# DroneController.net
KiCad netlist of a schematic drawn in EAGLE
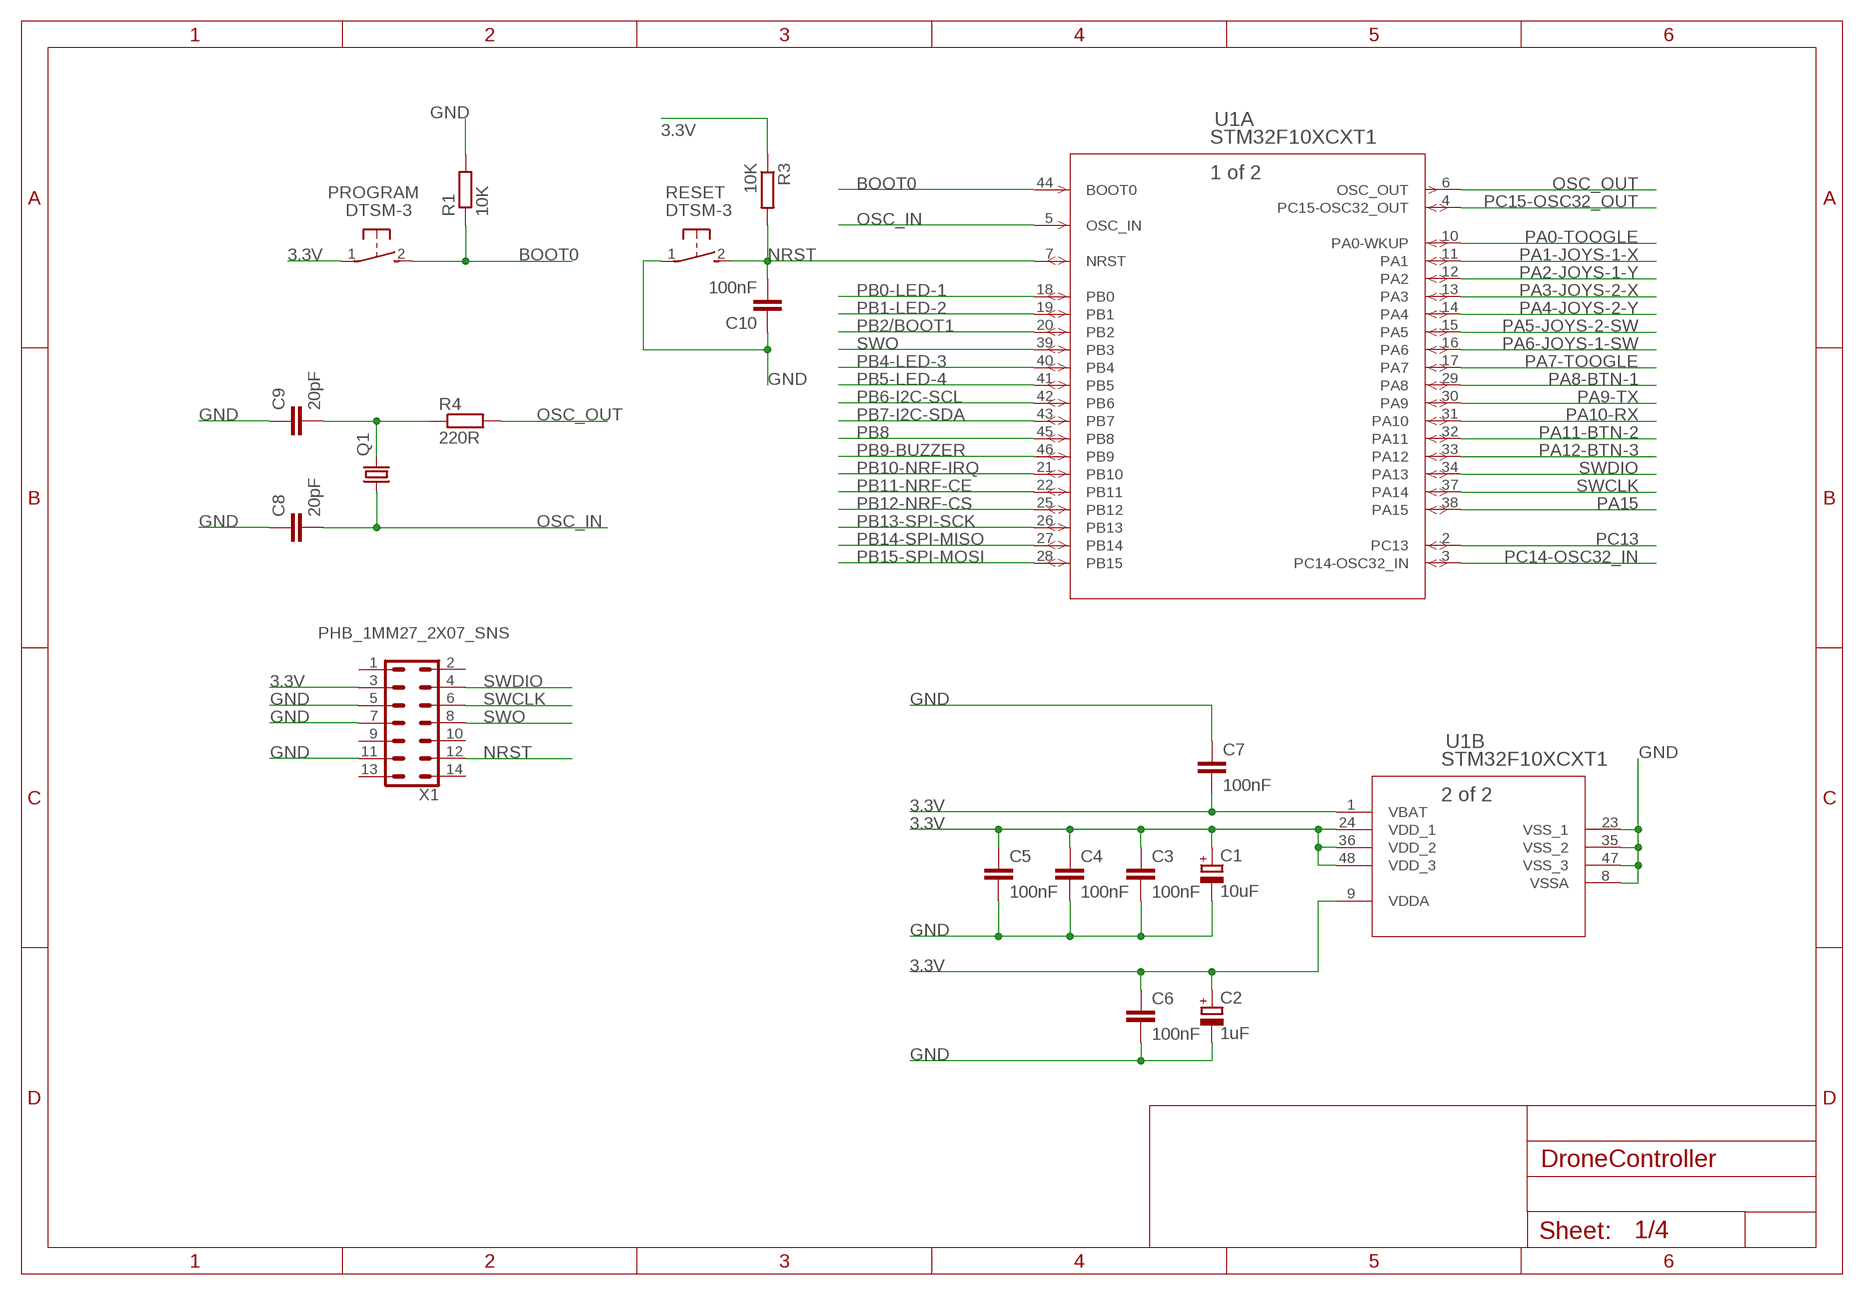
[diagram p0: schematic, sheet 1]
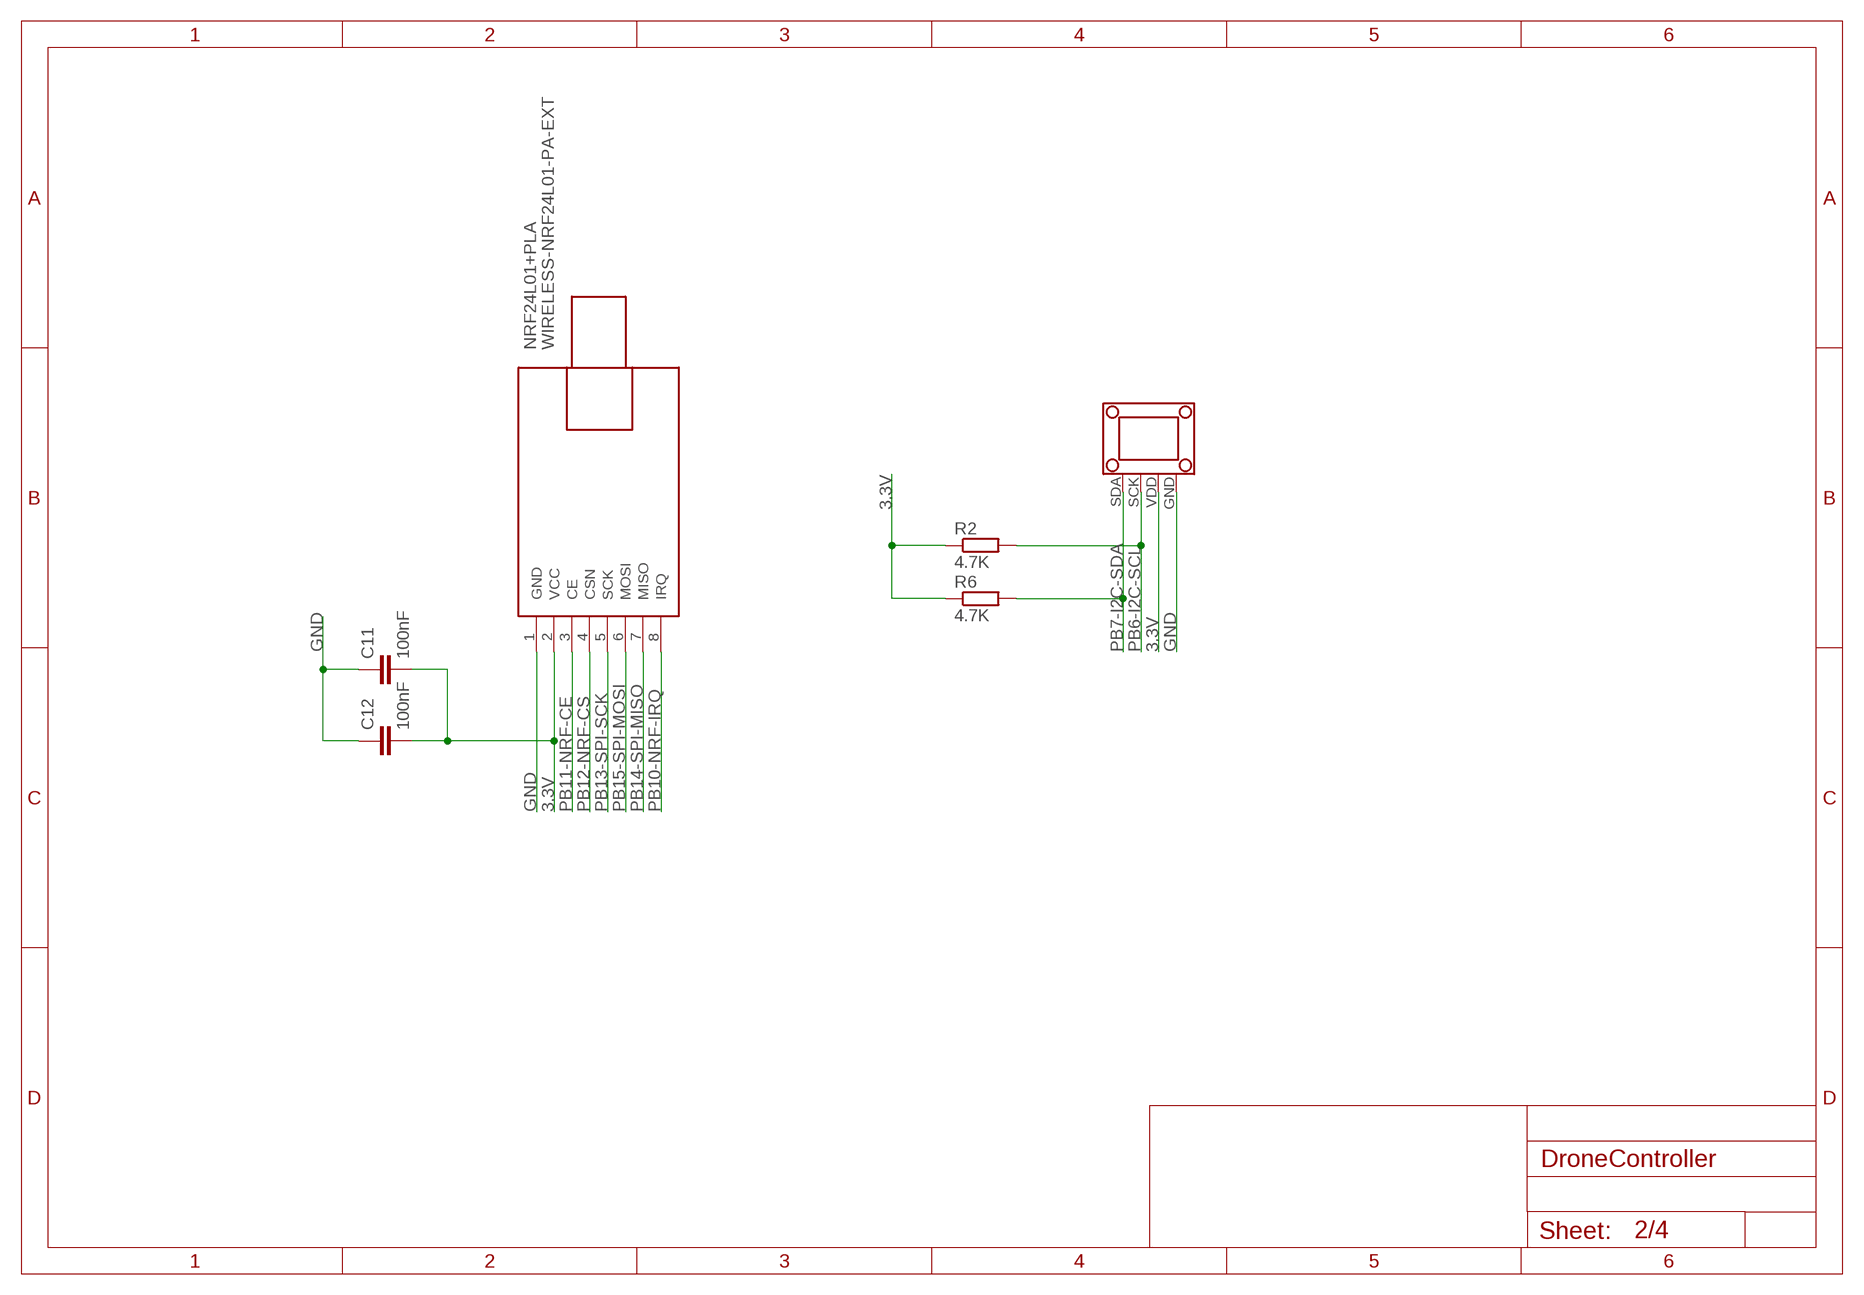
[diagram p1: schematic, sheet 2]
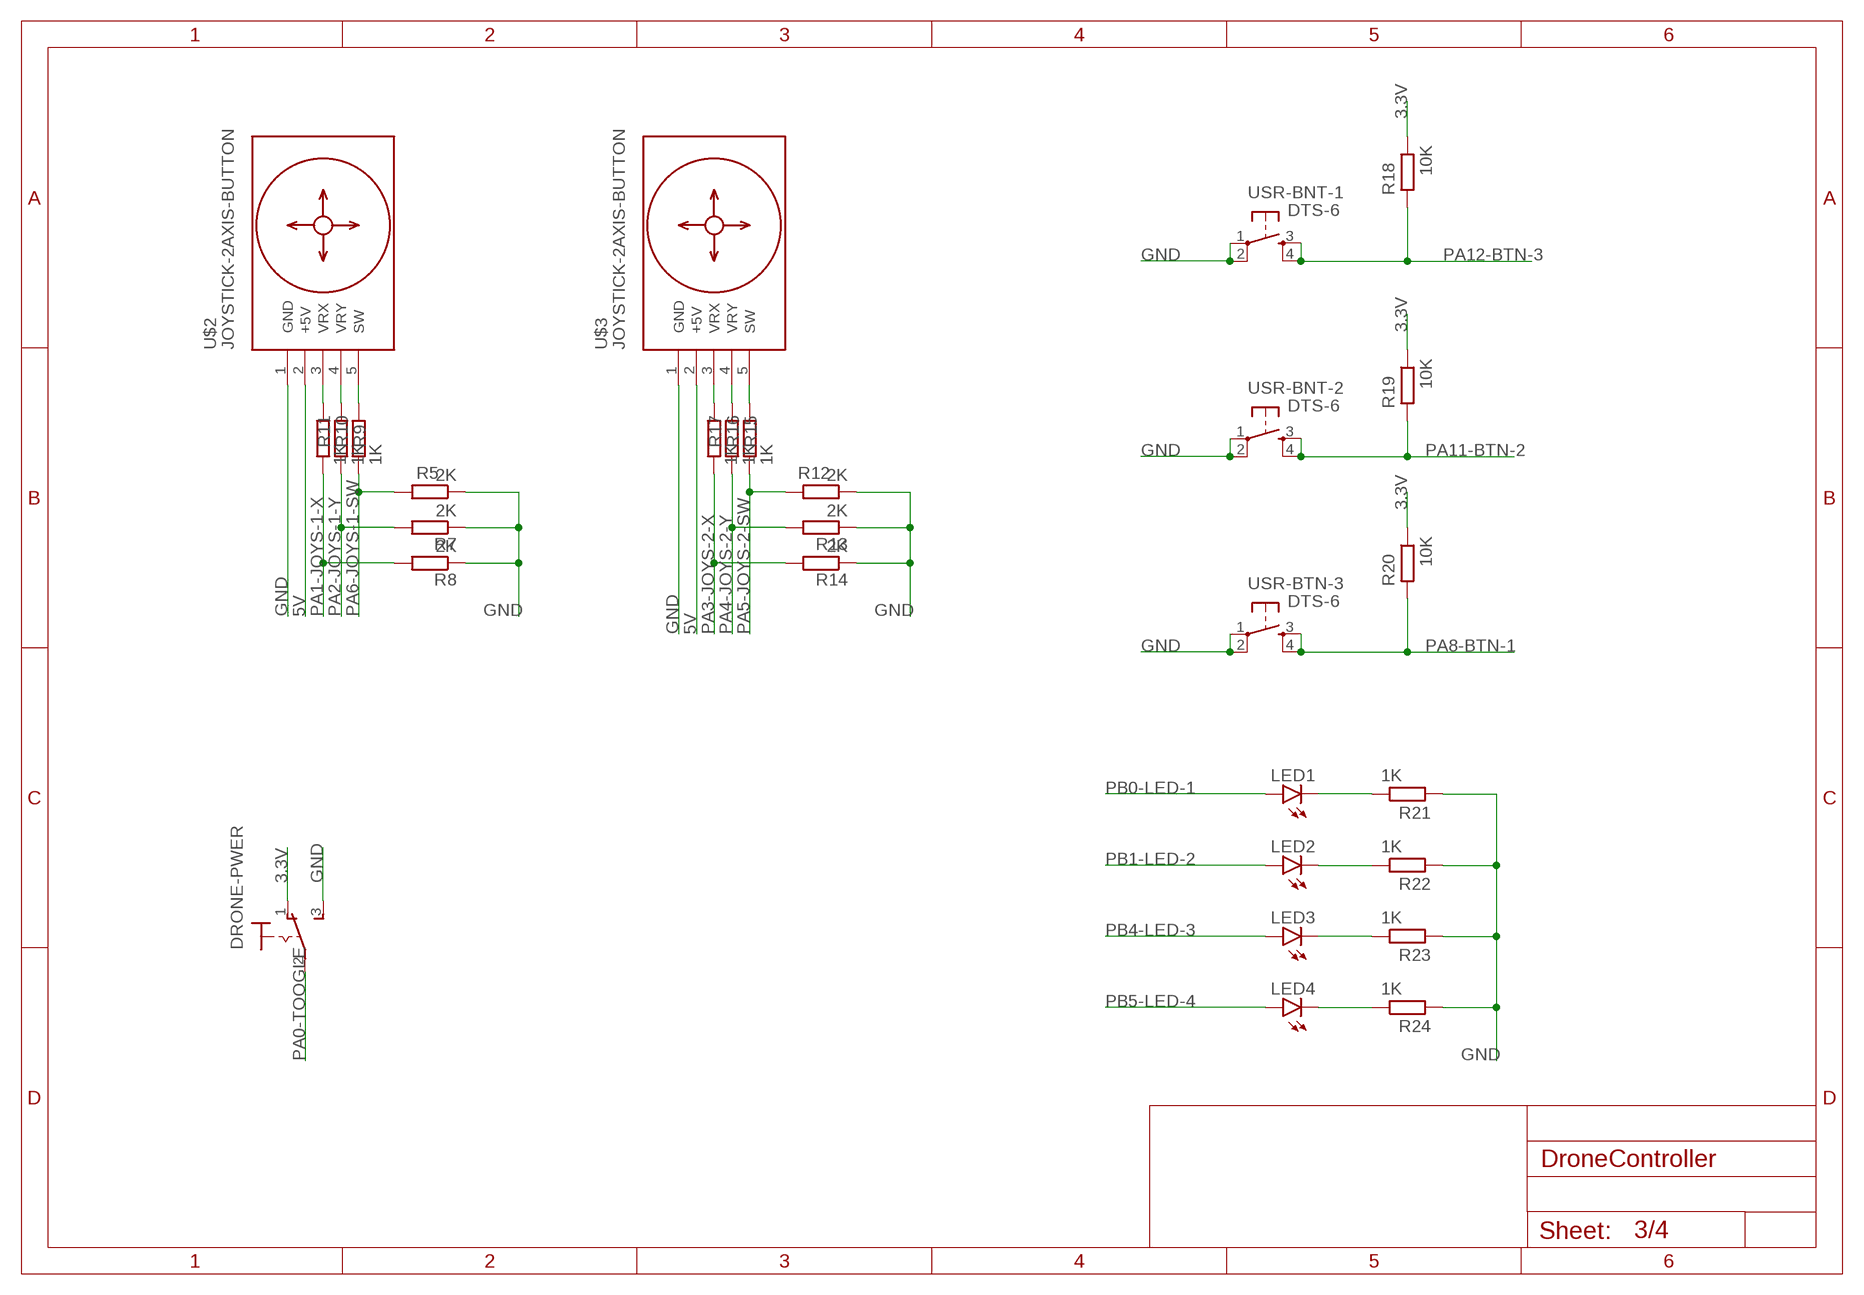
[diagram p2: schematic, sheet 3]
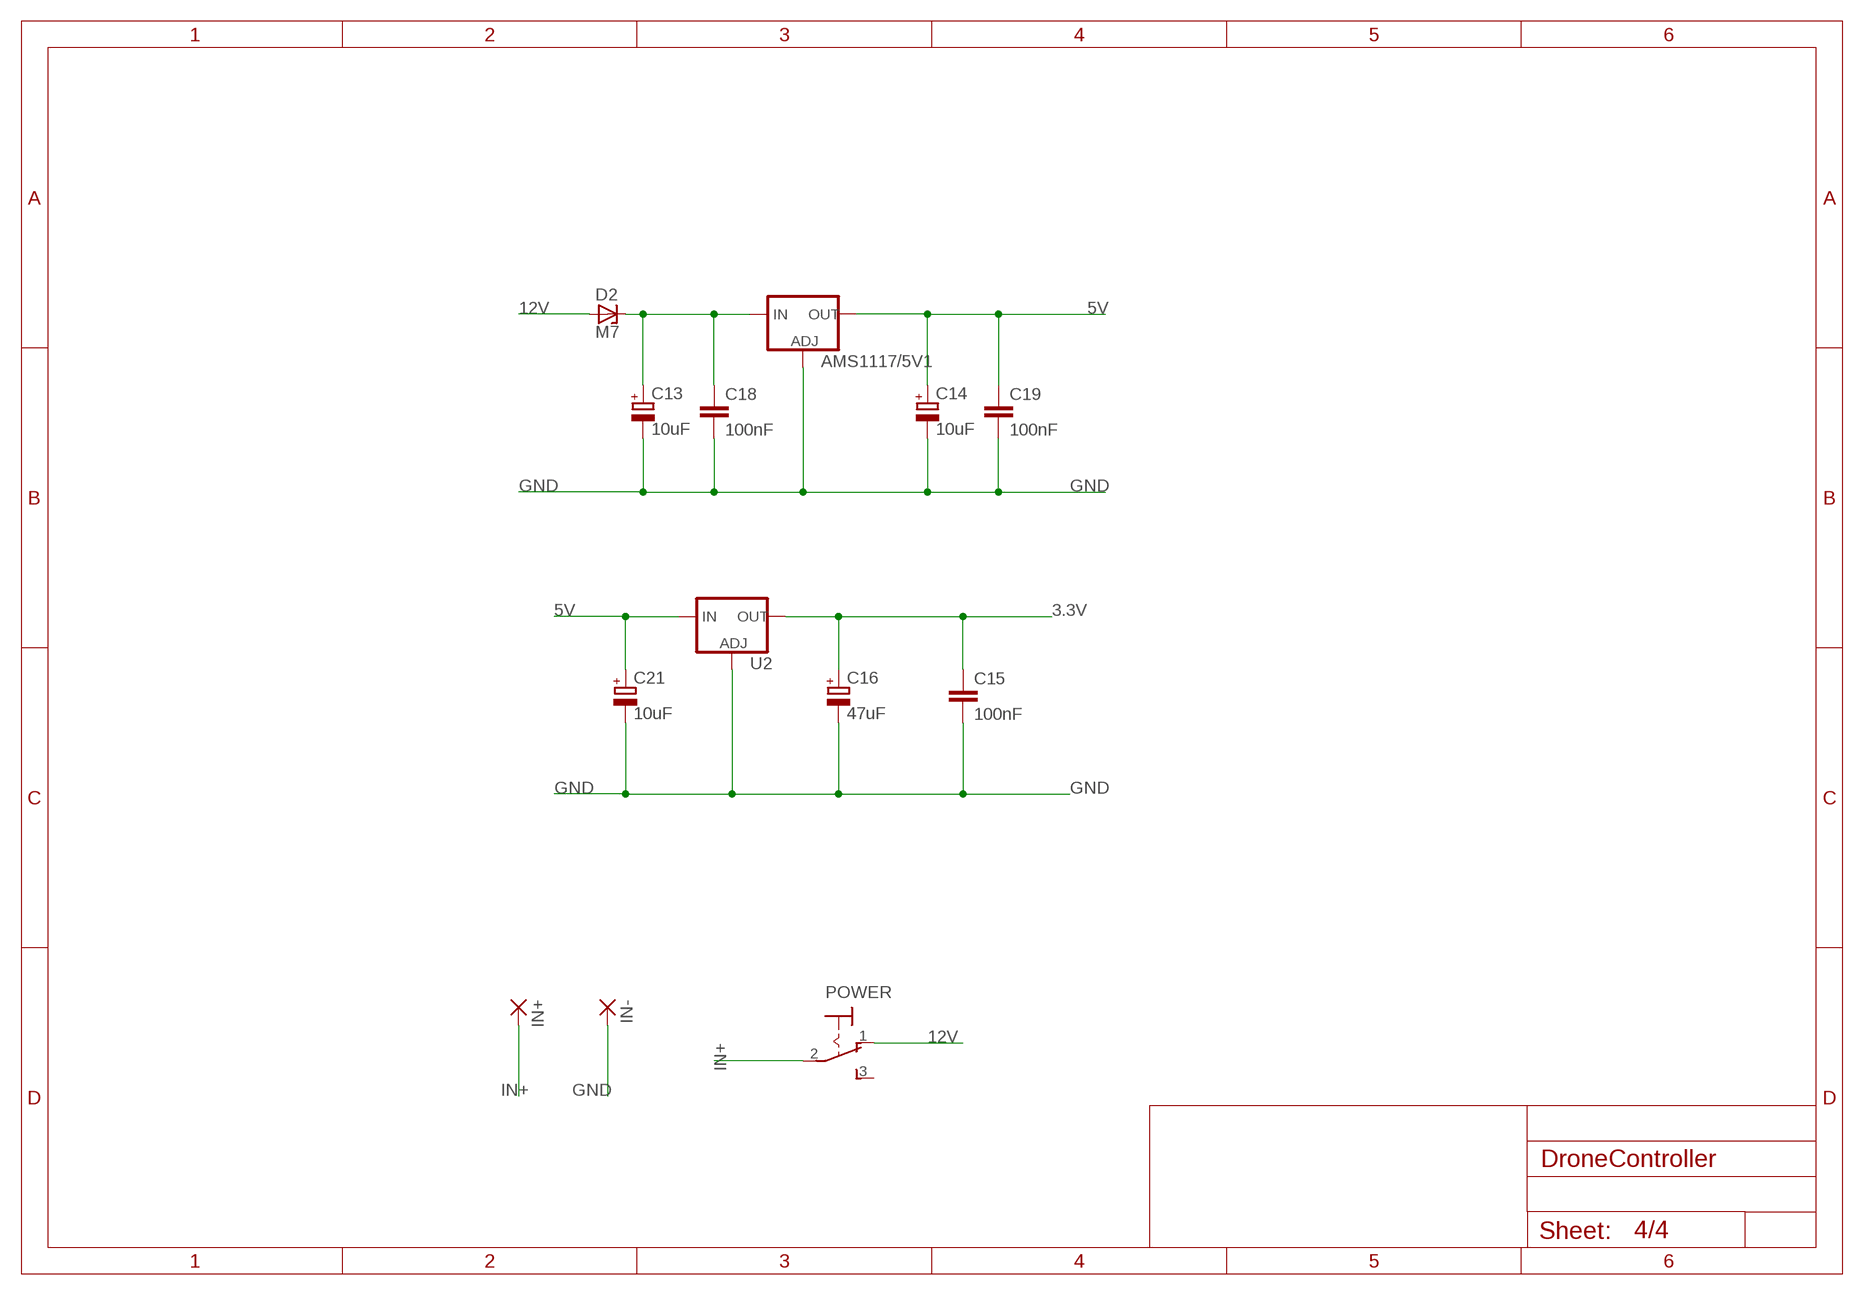
[diagram p3: schematic, sheet 4]

(export (version "E")
  (design (tool "Eeschema 10.0.6"))
  (components
    (comp (ref "DRONE-PWER")
      (value "M9040P")
      (footprint "eagle-import:M9040P")
      (libsource (lib "eagle-import") (part "M9040P"))
    )
    (comp (ref "LED1")
      (value "LEDCHIP-LED0805")
      (footprint "eagle-import:CHIP-LED0805")
      (libsource (lib "eagle-import") (part "LEDCHIP-LED0805"))
    )
    (comp (ref "LED2")
      (value "LEDCHIP-LED0805")
      (footprint "eagle-import:CHIP-LED0805")
      (libsource (lib "eagle-import") (part "LEDCHIP-LED0805"))
    )
    (comp (ref "LED3")
      (value "LEDCHIP-LED0805")
      (footprint "eagle-import:CHIP-LED0805")
      (libsource (lib "eagle-import") (part "LEDCHIP-LED0805"))
    )
    (comp (ref "LED4")
      (value "LEDCHIP-LED0805")
      (footprint "eagle-import:CHIP-LED0805")
      (libsource (lib "eagle-import") (part "LEDCHIP-LED0805"))
    )
    (comp (ref "R5")
      (value "2K")
      (footprint "eagle-import:R0805")
      (libsource (lib "eagle-import") (part "R-EU_R0805"))
    )
    (comp (ref "R7")
      (value "2K")
      (footprint "eagle-import:R0805")
      (libsource (lib "eagle-import") (part "R-EU_R0805"))
    )
    (comp (ref "R8")
      (value "2K")
      (footprint "eagle-import:R0805")
      (libsource (lib "eagle-import") (part "R-EU_R0805"))
    )
    (comp (ref "R9")
      (value "1K")
      (footprint "eagle-import:R0805")
      (libsource (lib "eagle-import") (part "R-EU_R0805"))
    )
    (comp (ref "R10")
      (value "1K")
      (footprint "eagle-import:R0805")
      (libsource (lib "eagle-import") (part "R-EU_R0805"))
    )
    (comp (ref "R11")
      (value "1K")
      (footprint "eagle-import:R0805")
      (libsource (lib "eagle-import") (part "R-EU_R0805"))
    )
    (comp (ref "R12")
      (value "2K")
      (footprint "eagle-import:R0805")
      (libsource (lib "eagle-import") (part "R-EU_R0805"))
    )
    (comp (ref "R13")
      (value "2K")
      (footprint "eagle-import:R0805")
      (libsource (lib "eagle-import") (part "R-EU_R0805"))
    )
    (comp (ref "R14")
      (value "2K")
      (footprint "eagle-import:R0805")
      (libsource (lib "eagle-import") (part "R-EU_R0805"))
    )
    (comp (ref "R15")
      (value "1K")
      (footprint "eagle-import:R0805")
      (libsource (lib "eagle-import") (part "R-EU_R0805"))
    )
    (comp (ref "R16")
      (value "1K")
      (footprint "eagle-import:R0805")
      (libsource (lib "eagle-import") (part "R-EU_R0805"))
    )
    (comp (ref "R17")
      (value "1K")
      (footprint "eagle-import:R0805")
      (libsource (lib "eagle-import") (part "R-EU_R0805"))
    )
    (comp (ref "R18")
      (value "10K")
      (footprint "eagle-import:R0805")
      (libsource (lib "eagle-import") (part "R-EU_R0805"))
    )
    (comp (ref "R19")
      (value "10K")
      (footprint "eagle-import:R0805")
      (libsource (lib "eagle-import") (part "R-EU_R0805"))
    )
    (comp (ref "R20")
      (value "10K")
      (footprint "eagle-import:R0805")
      (libsource (lib "eagle-import") (part "R-EU_R0805"))
    )
    (comp (ref "R21")
      (value "1K")
      (footprint "eagle-import:R0805")
      (libsource (lib "eagle-import") (part "R-EU_R0805"))
    )
    (comp (ref "R22")
      (value "1K")
      (footprint "eagle-import:R0805")
      (libsource (lib "eagle-import") (part "R-EU_R0805"))
    )
    (comp (ref "R23")
      (value "1K")
      (footprint "eagle-import:R0805")
      (libsource (lib "eagle-import") (part "R-EU_R0805"))
    )
    (comp (ref "R24")
      (value "1K")
      (footprint "eagle-import:R0805")
      (libsource (lib "eagle-import") (part "R-EU_R0805"))
    )
    (comp (ref "U$2")
      (value "JOYSTICK-2AXIS-BUTTON")
      (footprint "eagle-import:JOYSTICK-2AXIS-BUTTON")
      (libsource (lib "eagle-import") (part "JOYSTICK-2AXIS-BUTTON"))
    )
    (comp (ref "U$3")
      (value "JOYSTICK-2AXIS-BUTTON")
      (footprint "eagle-import:JOYSTICK-2AXIS-BUTTON")
      (libsource (lib "eagle-import") (part "JOYSTICK-2AXIS-BUTTON"))
    )
    (comp (ref "USR-BNT-1")
      (value "DTS-6")
      (footprint "eagle-import:DTS-6")
      (libsource (lib "eagle-import") (part "DTS-6"))
    )
    (comp (ref "USR-BNT-2")
      (value "DTS-6")
      (footprint "eagle-import:DTS-6")
      (libsource (lib "eagle-import") (part "DTS-6"))
    )
    (comp (ref "USR-BTN-3")
      (value "DTS-6")
      (footprint "eagle-import:DTS-6")
      (libsource (lib "eagle-import") (part "DTS-6"))
    )
    (comp (ref "AMS1117/5V1")
      (value "V_REG_LM1117SOT223")
      (footprint "eagle-import:SOT223")
      (libsource (lib "eagle-import") (part "V_REG_LM1117SOT223"))
    )
    (comp (ref "C13")
      (value "10uF")
      (footprint "eagle-import:SMC_A")
      (libsource (lib "eagle-import") (part "CPOL-EUSMCA"))
    )
    (comp (ref "C14")
      (value "10uF")
      (footprint "eagle-import:SMC_A")
      (libsource (lib "eagle-import") (part "CPOL-EUSMCA"))
    )
    (comp (ref "C15")
      (value "100nF")
      (footprint "eagle-import:C0805")
      (libsource (lib "eagle-import") (part "C-EUC0805"))
    )
    (comp (ref "C16")
      (value "47uF")
      (footprint "eagle-import:SMC_B")
      (libsource (lib "eagle-import") (part "CPOL-EUSMCB"))
    )
    (comp (ref "C18")
      (value "100nF")
      (footprint "eagle-import:C0805")
      (libsource (lib "eagle-import") (part "C-EUC0805"))
    )
    (comp (ref "C19")
      (value "100nF")
      (footprint "eagle-import:C0805")
      (libsource (lib "eagle-import") (part "C-EUC0805"))
    )
    (comp (ref "C21")
      (value "10uF")
      (footprint "eagle-import:SMC_A")
      (libsource (lib "eagle-import") (part "CPOL-EUSMCA"))
    )
    (comp (ref "D2")
      (value "M7")
      (footprint "eagle-import:DO214AC")
      (fields (field (name "MF") "ON Semiconductor") (field (name "MPN") "1SMA5913BT3G"))
      (libsource (lib "eagle-import") (part "1SMA59BT3G13"))
    )
    (comp (ref "IN+")
      (value "2,15/1,0")
      (footprint "eagle-import:2,15_1,0")
      (libsource (lib "eagle-import") (part "2,15/1,0"))
    )
    (comp (ref "IN-")
      (value "2,15/1,0")
      (footprint "eagle-import:2,15_1,0")
      (libsource (lib "eagle-import") (part "2,15/1,0"))
    )
    (comp (ref "POWER")
      (value "M9040P")
      (footprint "eagle-import:M9040P")
      (libsource (lib "eagle-import") (part "M9040P"))
    )
    (comp (ref "U2")
      (value "V_REG_LM1117SOT223")
      (footprint "eagle-import:SOT223")
      (libsource (lib "eagle-import") (part "V_REG_LM1117SOT223"))
    )
    (comp (ref "C11")
      (value "100nF")
      (footprint "eagle-import:C0805")
      (libsource (lib "eagle-import") (part "C-EUC0805"))
    )
    (comp (ref "C12")
      (value "100nF")
      (footprint "eagle-import:C0805")
      (libsource (lib "eagle-import") (part "C-EUC0805"))
    )
    (comp (ref "NRF24L01+PLA")
      (value "WIRELESS-NRF24L01-PA-EXT")
      (footprint "eagle-import:WIRELESS-NRF24L01-PA-EXT")
      (libsource (lib "eagle-import") (part "WIRELESS-NRF24L01-PA-EXT"))
    )
    (comp (ref "R2")
      (value "4.7K")
      (footprint "eagle-import:R0805")
      (libsource (lib "eagle-import") (part "R-EU_R0805"))
    )
    (comp (ref "R6")
      (value "4.7K")
      (footprint "eagle-import:R0805")
      (libsource (lib "eagle-import") (part "R-EU_R0805"))
    )
    (comp (ref "U$1")
      (value "1.3_TFT_OLED")
      (footprint "eagle-import:1.3_TFT_OLED")
      (libsource (lib "eagle-import") (part "1.3_TFT_OLED"))
    )
    (comp (ref "C1")
      (value "10uF")
      (footprint "eagle-import:SMC_A")
      (libsource (lib "eagle-import") (part "CPOL-EUSMCA"))
    )
    (comp (ref "C2")
      (value "1uF")
      (footprint "eagle-import:SMC_A")
      (libsource (lib "eagle-import") (part "CPOL-EUSMCA"))
    )
    (comp (ref "C3")
      (value "100nF")
      (footprint "eagle-import:C0805")
      (libsource (lib "eagle-import") (part "C-EUC0805"))
    )
    (comp (ref "C4")
      (value "100nF")
      (footprint "eagle-import:C0805")
      (libsource (lib "eagle-import") (part "C-EUC0805"))
    )
    (comp (ref "C5")
      (value "100nF")
      (footprint "eagle-import:C0805")
      (libsource (lib "eagle-import") (part "C-EUC0805"))
    )
    (comp (ref "C6")
      (value "100nF")
      (footprint "eagle-import:C0805")
      (libsource (lib "eagle-import") (part "C-EUC0805"))
    )
    (comp (ref "C7")
      (value "100nF")
      (footprint "eagle-import:C0805")
      (libsource (lib "eagle-import") (part "C-EUC0805"))
    )
    (comp (ref "C8")
      (value "20pF")
      (footprint "eagle-import:C0805")
      (libsource (lib "eagle-import") (part "C-EUC0805"))
    )
    (comp (ref "C9")
      (value "20pF")
      (footprint "eagle-import:C0805")
      (libsource (lib "eagle-import") (part "C-EUC0805"))
    )
    (comp (ref "C10")
      (value "100nF")
      (footprint "eagle-import:C0805")
      (libsource (lib "eagle-import") (part "C-EUC0805"))
    )
    (comp (ref "PROGRAM")
      (value "DTSM-3")
      (footprint "eagle-import:DTSM-3")
      (libsource (lib "eagle-import") (part "DTSM-3"))
    )
    (comp (ref "Q1")
      (value "CRYSTALHC49S")
      (footprint "eagle-import:HC49_S")
      (libsource (lib "eagle-import") (part "CRYSTALHC49S"))
    )
    (comp (ref "R1")
      (value "10K")
      (footprint "eagle-import:R0805")
      (libsource (lib "eagle-import") (part "R-EU_R0805"))
    )
    (comp (ref "R3")
      (value "10K")
      (footprint "eagle-import:R0805")
      (libsource (lib "eagle-import") (part "R-EU_R0805"))
    )
    (comp (ref "R4")
      (value "220R")
      (footprint "eagle-import:R0805")
      (libsource (lib "eagle-import") (part "R-EU_R0805"))
    )
    (comp (ref "RESET")
      (value "DTSM-3")
      (footprint "eagle-import:DTSM-3")
      (libsource (lib "eagle-import") (part "DTSM-3"))
    )
    (comp (ref "U1")
      (value "STM32F10XCXT1")
      (footprint "eagle-import:LQFP48-7X7MM")
      (fields (field (name "COPYRIGHT") "Copyright (C) 2016 Accelerated Designs. All rights reserved"))
      (libsource (lib "eagle-import") (part "STM32F10XCXT1"))
    )
    (comp (ref "X1")
      (value "PHB_1MM27_2X07_SNS")
      (footprint "eagle-import:PHB_1MM27_2X07_SNS")
      (libsource (lib "eagle-import") (part "PHB_1MM27_2X07_SNS"))
    )
  )
  (nets
    (net (code "1") (name "3.3V") (class "Default")
      (node (ref "C1") (pin "+") (pinfunction "+_+") (pintype "passive"))
      (node (ref "C11") (pin "2") (pinfunction "2_2") (pintype "passive"))
      (node (ref "C12") (pin "2") (pinfunction "2_2") (pintype "passive"))
      (node (ref "C15") (pin "1") (pinfunction "1_1") (pintype "passive"))
      (node (ref "C16") (pin "+") (pinfunction "+_+") (pintype "passive"))
      (node (ref "C2") (pin "+") (pinfunction "+_+") (pintype "passive"))
      (node (ref "C3") (pin "1") (pinfunction "1_1") (pintype "passive"))
      (node (ref "C4") (pin "1") (pinfunction "1_1") (pintype "passive"))
      (node (ref "C5") (pin "1") (pinfunction "1_1") (pintype "passive"))
      (node (ref "C6") (pin "1") (pinfunction "1_1") (pintype "passive"))
      (node (ref "C7") (pin "2") (pinfunction "2_2") (pintype "passive"))
      (node (ref "DRONE-PWER") (pin "1") (pinfunction "O_1") (pintype "passive"))
      (node (ref "NRF24L01+PLA") (pin "2") (pinfunction "VCC_2") (pintype "power_in"))
      (node (ref "PROGRAM") (pin "1") (pinfunction "1_1") (pintype "passive"))
      (node (ref "R18") (pin "1") (pinfunction "1_1") (pintype "passive"))
      (node (ref "R19") (pin "1") (pinfunction "1_1") (pintype "passive"))
      (node (ref "R2") (pin "1") (pinfunction "1_1") (pintype "passive"))
      (node (ref "R20") (pin "1") (pinfunction "1_1") (pintype "passive"))
      (node (ref "R3") (pin "1") (pinfunction "1_1") (pintype "passive"))
      (node (ref "R6") (pin "1") (pinfunction "1_1") (pintype "passive"))
      (node (ref "U$1") (pin "VDD") (pinfunction "VDD_VDD") (pintype "bidirectional"))
      (node (ref "U1") (pin "1") (pinfunction "VBAT_1") (pintype "power_in"))
      (node (ref "U1") (pin "24") (pinfunction "VDD_1_24") (pintype "power_in"))
      (node (ref "U1") (pin "36") (pinfunction "VDD_2_36") (pintype "power_in"))
      (node (ref "U1") (pin "48") (pinfunction "VDD_3_48") (pintype "power_in"))
      (node (ref "U1") (pin "9") (pinfunction "VDDA_9") (pintype "power_in"))
      (node (ref "U2") (pin "2") (pinfunction "OUT_2") (pintype "output"))
      (node (ref "U2") (pin "4") (pinfunction "OUT_4") (pintype "output"))
      (node (ref "X1") (pin "3") (pinfunction "3_3") (pintype "passive"))
    )
    (net (code "2") (name "5V") (class "Default")
      (node (ref "AMS1117/5V1") (pin "2") (pinfunction "OUT_2") (pintype "output"))
      (node (ref "AMS1117/5V1") (pin "4") (pinfunction "OUT_4") (pintype "output"))
      (node (ref "C14") (pin "+") (pinfunction "+_+") (pintype "passive"))
      (node (ref "C19") (pin "1") (pinfunction "1_1") (pintype "passive"))
      (node (ref "C21") (pin "+") (pinfunction "+_+") (pintype "passive"))
      (node (ref "U$2") (pin "2") (pinfunction "+5V_2") (pintype "power_in"))
      (node (ref "U$3") (pin "2") (pinfunction "+5V_2") (pintype "power_in"))
      (node (ref "U2") (pin "3") (pinfunction "IN_3") (pintype "input"))
    )
    (net (code "3") (name "12V") (class "Default")
      (node (ref "D2") (pin "A") (pinfunction "A_A") (pintype "passive"))
      (node (ref "POWER") (pin "1") (pinfunction "O_1") (pintype "passive"))
    )
    (net (code "4") (name "BOOT0") (class "Default")
      (node (ref "PROGRAM") (pin "2") (pinfunction "2_2") (pintype "passive"))
      (node (ref "R1") (pin "1") (pinfunction "1_1") (pintype "passive"))
      (node (ref "U1") (pin "44") (pinfunction "BOOT0_44") (pintype "input"))
    )
    (net (code "5") (name "GND") (class "Default")
      (node (ref "AMS1117/5V1") (pin "1") (pinfunction "ADJ_1") (pintype "input"))
      (node (ref "C1") (pin "-") (pinfunction "-_-") (pintype "passive"))
      (node (ref "C10") (pin "1") (pinfunction "1_1") (pintype "passive"))
      (node (ref "C11") (pin "1") (pinfunction "1_1") (pintype "passive"))
      (node (ref "C12") (pin "1") (pinfunction "1_1") (pintype "passive"))
      (node (ref "C13") (pin "-") (pinfunction "-_-") (pintype "passive"))
      (node (ref "C14") (pin "-") (pinfunction "-_-") (pintype "passive"))
      (node (ref "C15") (pin "2") (pinfunction "2_2") (pintype "passive"))
      (node (ref "C16") (pin "-") (pinfunction "-_-") (pintype "passive"))
      (node (ref "C18") (pin "2") (pinfunction "2_2") (pintype "passive"))
      (node (ref "C19") (pin "2") (pinfunction "2_2") (pintype "passive"))
      (node (ref "C2") (pin "-") (pinfunction "-_-") (pintype "passive"))
      (node (ref "C21") (pin "-") (pinfunction "-_-") (pintype "passive"))
      (node (ref "C3") (pin "2") (pinfunction "2_2") (pintype "passive"))
      (node (ref "C4") (pin "2") (pinfunction "2_2") (pintype "passive"))
      (node (ref "C5") (pin "2") (pinfunction "2_2") (pintype "passive"))
      (node (ref "C6") (pin "2") (pinfunction "2_2") (pintype "passive"))
      (node (ref "C7") (pin "1") (pinfunction "1_1") (pintype "passive"))
      (node (ref "C8") (pin "1") (pinfunction "1_1") (pintype "passive"))
      (node (ref "C9") (pin "1") (pinfunction "1_1") (pintype "passive"))
      (node (ref "DRONE-PWER") (pin "3") (pinfunction "S_3") (pintype "passive"))
      (node (ref "IN-") (pin "1") (pinfunction "P_1") (pintype "passive"))
      (node (ref "NRF24L01+PLA") (pin "1") (pinfunction "GND_1") (pintype "power_in"))
      (node (ref "R1") (pin "2") (pinfunction "2_2") (pintype "passive"))
      (node (ref "R12") (pin "1") (pinfunction "1_1") (pintype "passive"))
      (node (ref "R13") (pin "1") (pinfunction "1_1") (pintype "passive"))
      (node (ref "R14") (pin "1") (pinfunction "1_1") (pintype "passive"))
      (node (ref "R21") (pin "2") (pinfunction "2_2") (pintype "passive"))
      (node (ref "R22") (pin "2") (pinfunction "2_2") (pintype "passive"))
      (node (ref "R23") (pin "2") (pinfunction "2_2") (pintype "passive"))
      (node (ref "R24") (pin "2") (pinfunction "2_2") (pintype "passive"))
      (node (ref "R5") (pin "1") (pinfunction "1_1") (pintype "passive"))
      (node (ref "R7") (pin "1") (pinfunction "1_1") (pintype "passive"))
      (node (ref "R8") (pin "1") (pinfunction "1_1") (pintype "passive"))
      (node (ref "RESET") (pin "1") (pinfunction "1_1") (pintype "passive"))
      (node (ref "U$1") (pin "GND") (pinfunction "GND_GND") (pintype "bidirectional"))
      (node (ref "U$2") (pin "1") (pinfunction "GND_1") (pintype "power_in"))
      (node (ref "U$3") (pin "1") (pinfunction "GND_1") (pintype "power_in"))
      (node (ref "U1") (pin "23") (pinfunction "VSS_1_23") (pintype "power_in"))
      (node (ref "U1") (pin "35") (pinfunction "VSS_2_35") (pintype "power_in"))
      (node (ref "U1") (pin "47") (pinfunction "VSS_3_47") (pintype "power_in"))
      (node (ref "U1") (pin "8") (pinfunction "VSSA_8") (pintype "power_in"))
      (node (ref "U2") (pin "1") (pinfunction "ADJ_1") (pintype "input"))
      (node (ref "USR-BNT-1") (pin "1") (pinfunction "1_1") (pintype "passive"))
      (node (ref "USR-BNT-1") (pin "2") (pinfunction "2_2") (pintype "passive"))
      (node (ref "USR-BNT-2") (pin "1") (pinfunction "1_1") (pintype "passive"))
      (node (ref "USR-BNT-2") (pin "2") (pinfunction "2_2") (pintype "passive"))
      (node (ref "USR-BTN-3") (pin "1") (pinfunction "1_1") (pintype "passive"))
      (node (ref "USR-BTN-3") (pin "2") (pinfunction "2_2") (pintype "passive"))
      (node (ref "X1") (pin "11") (pinfunction "11_11") (pintype "passive"))
      (node (ref "X1") (pin "5") (pinfunction "5_5") (pintype "passive"))
      (node (ref "X1") (pin "7") (pinfunction "7_7") (pintype "passive"))
    )
    (net (code "6") (name "IN+") (class "Default")
      (node (ref "IN+") (pin "1") (pinfunction "P_1") (pintype "passive"))
      (node (ref "POWER") (pin "2") (pinfunction "P_2") (pintype "passive"))
    )
    (net (code "7") (name "NRST") (class "Default")
      (node (ref "C10") (pin "2") (pinfunction "2_2") (pintype "passive"))
      (node (ref "R3") (pin "2") (pinfunction "2_2") (pintype "passive"))
      (node (ref "RESET") (pin "2") (pinfunction "2_2") (pintype "passive"))
      (node (ref "U1") (pin "7") (pinfunction "NRST_7") (pintype "bidirectional"))
      (node (ref "X1") (pin "12") (pinfunction "12_12") (pintype "passive"))
    )
    (net (code "8") (name "Net-(AMS1117/5V1-IN)") (class "Default")
      (node (ref "AMS1117/5V1") (pin "3") (pinfunction "IN_3") (pintype "input"))
      (node (ref "C13") (pin "+") (pinfunction "+_+") (pintype "passive"))
      (node (ref "C18") (pin "1") (pinfunction "1_1") (pintype "passive"))
      (node (ref "D2") (pin "C") (pinfunction "C_C") (pintype "passive"))
    )
    (net (code "9") (name "Net-(C9-Pad2)") (class "Default")
      (node (ref "C9") (pin "2") (pinfunction "2_2") (pintype "passive"))
      (node (ref "Q1") (pin "2") (pinfunction "2_2") (pintype "passive"))
      (node (ref "R4") (pin "1") (pinfunction "1_1") (pintype "passive"))
    )
    (net (code "10") (name "Net-(LED1-PadC)") (class "Default")
      (node (ref "LED1") (pin "C") (pinfunction "C_C") (pintype "passive"))
      (node (ref "R21") (pin "1") (pinfunction "1_1") (pintype "passive"))
    )
    (net (code "11") (name "Net-(LED2-PadC)") (class "Default")
      (node (ref "LED2") (pin "C") (pinfunction "C_C") (pintype "passive"))
      (node (ref "R22") (pin "1") (pinfunction "1_1") (pintype "passive"))
    )
    (net (code "12") (name "Net-(LED3-PadC)") (class "Default")
      (node (ref "LED3") (pin "C") (pinfunction "C_C") (pintype "passive"))
      (node (ref "R23") (pin "1") (pinfunction "1_1") (pintype "passive"))
    )
    (net (code "13") (name "Net-(LED4-PadC)") (class "Default")
      (node (ref "LED4") (pin "C") (pinfunction "C_C") (pintype "passive"))
      (node (ref "R24") (pin "1") (pinfunction "1_1") (pintype "passive"))
    )
    (net (code "14") (name "Net-(U$2-SW)") (class "Default")
      (node (ref "R9") (pin "2") (pinfunction "2_2") (pintype "passive"))
      (node (ref "U$2") (pin "5") (pinfunction "SW_5") (pintype "passive"))
    )
    (net (code "15") (name "Net-(U$2-VRX)") (class "Default")
      (node (ref "R11") (pin "2") (pinfunction "2_2") (pintype "passive"))
      (node (ref "U$2") (pin "3") (pinfunction "VRX_3") (pintype "passive"))
    )
    (net (code "16") (name "Net-(U$2-VRY)") (class "Default")
      (node (ref "R10") (pin "2") (pinfunction "2_2") (pintype "passive"))
      (node (ref "U$2") (pin "4") (pinfunction "VRY_4") (pintype "passive"))
    )
    (net (code "17") (name "Net-(U$3-SW)") (class "Default")
      (node (ref "R15") (pin "2") (pinfunction "2_2") (pintype "passive"))
      (node (ref "U$3") (pin "5") (pinfunction "SW_5") (pintype "passive"))
    )
    (net (code "18") (name "Net-(U$3-VRX)") (class "Default")
      (node (ref "R17") (pin "2") (pinfunction "2_2") (pintype "passive"))
      (node (ref "U$3") (pin "3") (pinfunction "VRX_3") (pintype "passive"))
    )
    (net (code "19") (name "Net-(U$3-VRY)") (class "Default")
      (node (ref "R16") (pin "2") (pinfunction "2_2") (pintype "passive"))
      (node (ref "U$3") (pin "4") (pinfunction "VRY_4") (pintype "passive"))
    )
    (net (code "20") (name "OSC_IN") (class "Default")
      (node (ref "C8") (pin "2") (pinfunction "2_2") (pintype "passive"))
      (node (ref "Q1") (pin "1") (pinfunction "1_1") (pintype "passive"))
      (node (ref "U1") (pin "5") (pinfunction "OSC_IN_5") (pintype "input"))
    )
    (net (code "21") (name "OSC_OUT") (class "Default")
      (node (ref "R4") (pin "2") (pinfunction "2_2") (pintype "passive"))
      (node (ref "U1") (pin "6") (pinfunction "OSC_OUT_6") (pintype "output"))
    )
    (net (code "22") (name "PA0-TOOGLE") (class "Default")
      (node (ref "DRONE-PWER") (pin "2") (pinfunction "P_2") (pintype "passive"))
      (node (ref "U1") (pin "10") (pinfunction "PA0-WKUP_10") (pintype "bidirectional"))
    )
    (net (code "23") (name "PA1-JOYS-1-X") (class "Default")
      (node (ref "R11") (pin "1") (pinfunction "1_1") (pintype "passive"))
      (node (ref "R8") (pin "2") (pinfunction "2_2") (pintype "passive"))
      (node (ref "U1") (pin "11") (pinfunction "PA1_11") (pintype "bidirectional"))
    )
    (net (code "24") (name "PA2-JOYS-1-Y") (class "Default")
      (node (ref "R10") (pin "1") (pinfunction "1_1") (pintype "passive"))
      (node (ref "R7") (pin "2") (pinfunction "2_2") (pintype "passive"))
      (node (ref "U1") (pin "12") (pinfunction "PA2_12") (pintype "bidirectional"))
    )
    (net (code "25") (name "PA3-JOYS-2-X") (class "Default")
      (node (ref "R14") (pin "2") (pinfunction "2_2") (pintype "passive"))
      (node (ref "R17") (pin "1") (pinfunction "1_1") (pintype "passive"))
      (node (ref "U1") (pin "13") (pinfunction "PA3_13") (pintype "bidirectional"))
    )
    (net (code "26") (name "PA4-JOYS-2-Y") (class "Default")
      (node (ref "R13") (pin "2") (pinfunction "2_2") (pintype "passive"))
      (node (ref "R16") (pin "1") (pinfunction "1_1") (pintype "passive"))
      (node (ref "U1") (pin "14") (pinfunction "PA4_14") (pintype "bidirectional"))
    )
    (net (code "27") (name "PA5-JOYS-2-SW") (class "Default")
      (node (ref "R12") (pin "2") (pinfunction "2_2") (pintype "passive"))
      (node (ref "R15") (pin "1") (pinfunction "1_1") (pintype "passive"))
      (node (ref "U1") (pin "15") (pinfunction "PA5_15") (pintype "bidirectional"))
    )
    (net (code "28") (name "PA6-JOYS-1-SW") (class "Default")
      (node (ref "R5") (pin "2") (pinfunction "2_2") (pintype "passive"))
      (node (ref "R9") (pin "1") (pinfunction "1_1") (pintype "passive"))
      (node (ref "U1") (pin "16") (pinfunction "PA6_16") (pintype "bidirectional"))
    )
    (net (code "29") (name "PA7-TOOGLE") (class "Default")
      (node (ref "U1") (pin "17") (pinfunction "PA7_17") (pintype "bidirectional"))
    )
    (net (code "30") (name "PA8-BTN-1") (class "Default")
      (node (ref "R20") (pin "2") (pinfunction "2_2") (pintype "passive"))
      (node (ref "U1") (pin "29") (pinfunction "PA8_29") (pintype "bidirectional"))
      (node (ref "USR-BTN-3") (pin "3") (pinfunction "3_3") (pintype "passive"))
      (node (ref "USR-BTN-3") (pin "4") (pinfunction "4_4") (pintype "passive"))
    )
    (net (code "31") (name "PA9-TX") (class "Default")
      (node (ref "U1") (pin "30") (pinfunction "PA9_30") (pintype "bidirectional"))
    )
    (net (code "32") (name "PA10-RX") (class "Default")
      (node (ref "U1") (pin "31") (pinfunction "PA10_31") (pintype "bidirectional"))
    )
    (net (code "33") (name "PA11-BTN-2") (class "Default")
      (node (ref "R19") (pin "2") (pinfunction "2_2") (pintype "passive"))
      (node (ref "U1") (pin "32") (pinfunction "PA11_32") (pintype "bidirectional"))
      (node (ref "USR-BNT-2") (pin "3") (pinfunction "3_3") (pintype "passive"))
      (node (ref "USR-BNT-2") (pin "4") (pinfunction "4_4") (pintype "passive"))
    )
    (net (code "34") (name "PA12-BTN-3") (class "Default")
      (node (ref "R18") (pin "2") (pinfunction "2_2") (pintype "passive"))
      (node (ref "U1") (pin "33") (pinfunction "PA12_33") (pintype "bidirectional"))
      (node (ref "USR-BNT-1") (pin "3") (pinfunction "3_3") (pintype "passive"))
      (node (ref "USR-BNT-1") (pin "4") (pinfunction "4_4") (pintype "passive"))
    )
    (net (code "35") (name "PA15") (class "Default")
      (node (ref "U1") (pin "38") (pinfunction "PA15_38") (pintype "bidirectional"))
    )
    (net (code "36") (name "PB0-LED-1") (class "Default")
      (node (ref "LED1") (pin "A") (pinfunction "A_A") (pintype "passive"))
      (node (ref "U1") (pin "18") (pinfunction "PB0_18") (pintype "bidirectional"))
    )
    (net (code "37") (name "PB1-LED-2") (class "Default")
      (node (ref "LED2") (pin "A") (pinfunction "A_A") (pintype "passive"))
      (node (ref "U1") (pin "19") (pinfunction "PB1_19") (pintype "bidirectional"))
    )
    (net (code "38") (name "PB2{slash}BOOT1") (class "Default")
      (node (ref "U1") (pin "20") (pinfunction "PB2_20") (pintype "bidirectional"))
    )
    (net (code "39") (name "PB4-LED-3") (class "Default")
      (node (ref "LED3") (pin "A") (pinfunction "A_A") (pintype "passive"))
      (node (ref "U1") (pin "40") (pinfunction "PB4_40") (pintype "bidirectional"))
    )
    (net (code "40") (name "PB5-LED-4") (class "Default")
      (node (ref "LED4") (pin "A") (pinfunction "A_A") (pintype "passive"))
      (node (ref "U1") (pin "41") (pinfunction "PB5_41") (pintype "bidirectional"))
    )
    (net (code "41") (name "PB6-I2C-SCL") (class "Default")
      (node (ref "R2") (pin "2") (pinfunction "2_2") (pintype "passive"))
      (node (ref "U$1") (pin "SCK") (pinfunction "SCK_SCK") (pintype "bidirectional"))
      (node (ref "U1") (pin "42") (pinfunction "PB6_42") (pintype "bidirectional"))
    )
    (net (code "42") (name "PB7-I2C-SDA") (class "Default")
      (node (ref "R6") (pin "2") (pinfunction "2_2") (pintype "passive"))
      (node (ref "U$1") (pin "SDA") (pinfunction "SDA_SDA") (pintype "bidirectional"))
      (node (ref "U1") (pin "43") (pinfunction "PB7_43") (pintype "bidirectional"))
    )
    (net (code "43") (name "PB8") (class "Default")
      (node (ref "U1") (pin "45") (pinfunction "PB8_45") (pintype "bidirectional"))
    )
    (net (code "44") (name "PB9-BUZZER") (class "Default")
      (node (ref "U1") (pin "46") (pinfunction "PB9_46") (pintype "bidirectional"))
    )
    (net (code "45") (name "PB10-NRF-IRQ") (class "Default")
      (node (ref "NRF24L01+PLA") (pin "8") (pinfunction "IRQ_8") (pintype "bidirectional"))
      (node (ref "U1") (pin "21") (pinfunction "PB10_21") (pintype "bidirectional"))
    )
    (net (code "46") (name "PB11-NRF-CE") (class "Default")
      (node (ref "NRF24L01+PLA") (pin "3") (pinfunction "CE_3") (pintype "bidirectional"))
      (node (ref "U1") (pin "22") (pinfunction "PB11_22") (pintype "bidirectional"))
    )
    (net (code "47") (name "PB12-NRF-CS") (class "Default")
      (node (ref "NRF24L01+PLA") (pin "4") (pinfunction "CSN_4") (pintype "bidirectional"))
      (node (ref "U1") (pin "25") (pinfunction "PB12_25") (pintype "bidirectional"))
    )
    (net (code "48") (name "PB13-SPI-SCK") (class "Default")
      (node (ref "NRF24L01+PLA") (pin "5") (pinfunction "SCK_5") (pintype "bidirectional"))
      (node (ref "U1") (pin "26") (pinfunction "PB13_26") (pintype "bidirectional"))
    )
    (net (code "49") (name "PB14-SPI-MISO") (class "Default")
      (node (ref "NRF24L01+PLA") (pin "7") (pinfunction "MISO_7") (pintype "bidirectional"))
      (node (ref "U1") (pin "27") (pinfunction "PB14_27") (pintype "bidirectional"))
    )
    (net (code "50") (name "PB15-SPI-MOSI") (class "Default")
      (node (ref "NRF24L01+PLA") (pin "6") (pinfunction "MOSI_6") (pintype "bidirectional"))
      (node (ref "U1") (pin "28") (pinfunction "PB15_28") (pintype "bidirectional"))
    )
    (net (code "51") (name "PC13") (class "Default")
      (node (ref "U1") (pin "2") (pinfunction "PC13_2") (pintype "bidirectional"))
    )
    (net (code "52") (name "PC14-OSC32_IN") (class "Default")
      (node (ref "U1") (pin "3") (pinfunction "PC14-OSC32_IN_3") (pintype "bidirectional"))
    )
    (net (code "53") (name "PC15-OSC32_OUT") (class "Default")
      (node (ref "U1") (pin "4") (pinfunction "PC15-OSC32_OUT_4") (pintype "bidirectional"))
    )
    (net (code "54") (name "SWCLK") (class "Default")
      (node (ref "U1") (pin "37") (pinfunction "PA14_37") (pintype "bidirectional"))
      (node (ref "X1") (pin "6") (pinfunction "6_6") (pintype "passive"))
    )
    (net (code "55") (name "SWDIO") (class "Default")
      (node (ref "U1") (pin "34") (pinfunction "PA13_34") (pintype "bidirectional"))
      (node (ref "X1") (pin "4") (pinfunction "4_4") (pintype "passive"))
    )
    (net (code "56") (name "SWO") (class "Default")
      (node (ref "U1") (pin "39") (pinfunction "PB3_39") (pintype "bidirectional"))
      (node (ref "X1") (pin "8") (pinfunction "8_8") (pintype "passive"))
    )
    (net (code "57") (name "unconnected-(POWER-S-Pad3)") (class "Default")
      (node (ref "POWER") (pin "3") (pinfunction "S_3") (pintype "passive"))
    )
    (net (code "58") (name "unconnected-(X1-Pad1)") (class "Default")
      (node (ref "X1") (pin "1") (pinfunction "1_1") (pintype "passive"))
    )
    (net (code "59") (name "unconnected-(X1-Pad2)") (class "Default")
      (node (ref "X1") (pin "2") (pinfunction "2_2") (pintype "passive"))
    )
    (net (code "60") (name "unconnected-(X1-Pad9)") (class "Default")
      (node (ref "X1") (pin "9") (pinfunction "9_9") (pintype "passive"))
    )
    (net (code "61") (name "unconnected-(X1-Pad10)") (class "Default")
      (node (ref "X1") (pin "10") (pinfunction "10_10") (pintype "passive"))
    )
    (net (code "62") (name "unconnected-(X1-Pad13)") (class "Default")
      (node (ref "X1") (pin "13") (pinfunction "13_13") (pintype "passive"))
    )
    (net (code "63") (name "unconnected-(X1-Pad14)") (class "Default")
      (node (ref "X1") (pin "14") (pinfunction "14_14") (pintype "passive"))
    )
  )
)
